# CLKs.net
KiCad netlist of a schematic drawn in Altium Designer
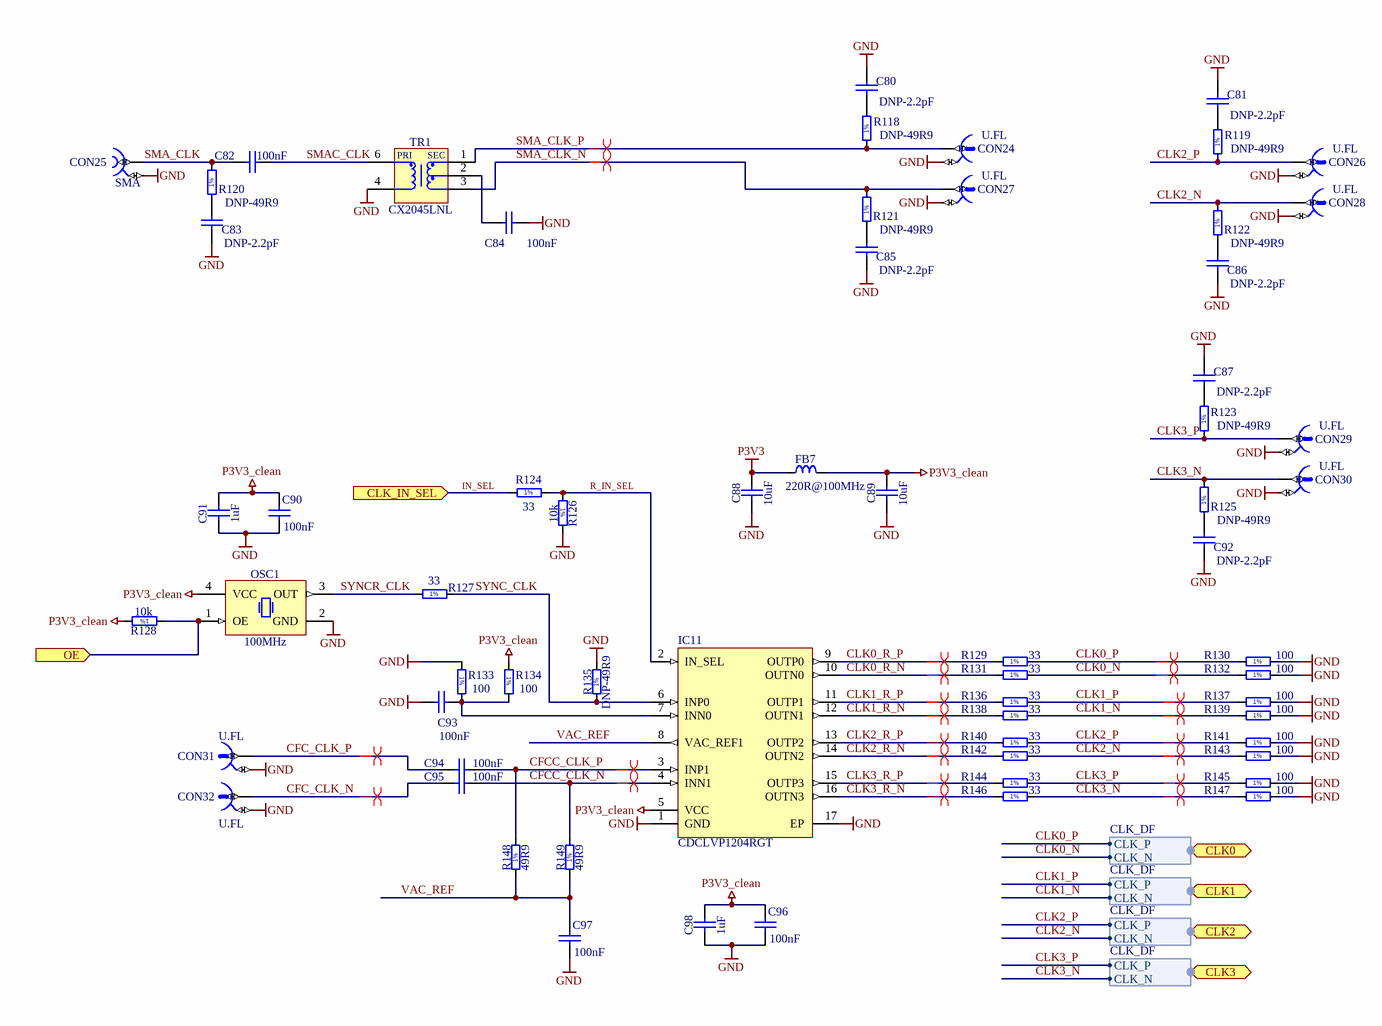
[diagram p0: CLKs.SchDoc]

(export (version "E")
  (design (tool "Eeschema 10.0.6"))
  (components
    (comp (ref "C80")
      (value "DNP-2.2pF")
      (footprint "CAPC1005X55N")
      (description "Non-polarised capacitor")
      (fields
        (field (name "PART NUMBER") "CC0402_2.2PF_50V_0.25PF_NP0")
        (field (name "VOLTAGE") "50V")
        (field (name "AUTHOR") "CERN DEM JLC")
      )
      (libsource (lib "Capacitors") (part "Capacitor - non polarized"))
    )
    (comp (ref "C81")
      (value "DNP-2.2pF")
      (footprint "CAPC1005X55N")
      (description "Non-polarised capacitor")
      (fields
        (field (name "PART NUMBER") "CC0402_2.2PF_50V_0.25PF_NP0")
        (field (name "VOLTAGE") "50V")
        (field (name "AUTHOR") "CERN DEM JLC")
      )
      (libsource (lib "Capacitors") (part "Capacitor - non polarized"))
    )
    (comp (ref "C82")
      (value "100nF")
      (footprint "CAPC0603X33N")
      (description "Non-polarised capacitor")
      (fields
        (field (name "PART NUMBER") "CC0201_100NF_6.3V_10%_X5R")
        (field (name "VOLTAGE") "6.3V")
        (field (name "AUTHOR") "CERN DEM JLC")
      )
      (libsource (lib "Capacitors") (part "Capacitor - non polarized"))
    )
    (comp (ref "C83")
      (value "DNP-2.2pF")
      (footprint "CAPC1005X55N")
      (description "Non-polarised capacitor")
      (fields
        (field (name "PART NUMBER") "CC0402_2.2PF_50V_0.25PF_NP0")
        (field (name "VOLTAGE") "50V")
        (field (name "AUTHOR") "CERN DEM JLC")
      )
      (libsource (lib "Capacitors") (part "Capacitor - non polarized"))
    )
    (comp (ref "C84")
      (value "100nF")
      (footprint "CAPC0603X33N")
      (description "Non-polarised capacitor")
      (fields
        (field (name "PART NUMBER") "CC0201_100NF_6.3V_10%_X5R")
        (field (name "VOLTAGE") "6.3V")
        (field (name "AUTHOR") "CERN DEM JLC")
      )
      (libsource (lib "Capacitors") (part "Capacitor - non polarized"))
    )
    (comp (ref "C85")
      (value "DNP-2.2pF")
      (footprint "CAPC1005X55N")
      (description "Non-polarised capacitor")
      (fields
        (field (name "PART NUMBER") "CC0402_2.2PF_50V_0.25PF_NP0")
        (field (name "VOLTAGE") "50V")
        (field (name "AUTHOR") "CERN DEM JLC")
      )
      (libsource (lib "Capacitors") (part "Capacitor - non polarized"))
    )
    (comp (ref "C86")
      (value "DNP-2.2pF")
      (footprint "CAPC1005X55N")
      (description "Non-polarised capacitor")
      (fields
        (field (name "PART NUMBER") "CC0402_2.2PF_50V_0.25PF_NP0")
        (field (name "VOLTAGE") "50V")
        (field (name "AUTHOR") "CERN DEM JLC")
      )
      (libsource (lib "Capacitors") (part "Capacitor - non polarized"))
    )
    (comp (ref "C87")
      (value "DNP-2.2pF")
      (footprint "CAPC1005X55N")
      (description "Non-polarised capacitor")
      (fields
        (field (name "PART NUMBER") "CC0402_2.2PF_50V_0.25PF_NP0")
        (field (name "VOLTAGE") "50V")
        (field (name "AUTHOR") "CERN DEM JLC")
      )
      (libsource (lib "Capacitors") (part "Capacitor - non polarized"))
    )
    (comp (ref "C88")
      (value "10uF")
      (footprint "CAPC2012X135N")
      (description "Non-polarised capacitor")
      (fields
        (field (name "PART NUMBER") "CC0805_10UF_10V_10%_X7R")
        (field (name "VOLTAGE") "10V")
        (field (name "AUTHOR") "CERN DEM JLC")
      )
      (libsource (lib "Capacitors") (part "Capacitor - non polarized"))
    )
    (comp (ref "C89")
      (value "10uF")
      (footprint "CAPC2012X135N")
      (description "Non-polarised capacitor")
      (fields
        (field (name "PART NUMBER") "CC0805_10UF_10V_10%_X7R")
        (field (name "VOLTAGE") "10V")
        (field (name "AUTHOR") "CERN DEM JLC")
      )
      (libsource (lib "Capacitors") (part "Capacitor - non polarized"))
    )
    (comp (ref "C90")
      (value "100nF")
      (footprint "CAPC0603X33N")
      (description "Non-polarised capacitor")
      (fields
        (field (name "PART NUMBER") "CC0201_100NF_6.3V_10%_X5R")
        (field (name "VOLTAGE") "6.3V")
        (field (name "AUTHOR") "CERN DEM JLC")
      )
      (libsource (lib "Capacitors") (part "Capacitor - non polarized"))
    )
    (comp (ref "C91")
      (value "1uF")
      (footprint "CAPC1608X87N")
      (description "Non-polarised capacitor")
      (fields
        (field (name "PART NUMBER") "CC0603_1UF_25V_10%_X7R")
        (field (name "VOLTAGE") "25V")
        (field (name "AUTHOR") "CERN DEM JLC")
      )
      (libsource (lib "Capacitors") (part "Capacitor - non polarized"))
    )
    (comp (ref "C92")
      (value "DNP-2.2pF")
      (footprint "CAPC1005X55N")
      (description "Non-polarised capacitor")
      (fields
        (field (name "PART NUMBER") "CC0402_2.2PF_50V_0.25PF_NP0")
        (field (name "VOLTAGE") "50V")
        (field (name "AUTHOR") "CERN DEM JLC")
      )
      (libsource (lib "Capacitors") (part "Capacitor - non polarized"))
    )
    (comp (ref "C93")
      (value "100nF")
      (footprint "CAPC1005X55N")
      (description "Non-polarised capacitor")
      (fields
        (field (name "PART NUMBER") "CC0402_100NF_16V_10%_X7R")
        (field (name "VOLTAGE") "16V")
        (field (name "AUTHOR") "CERN DEM JLC")
      )
      (libsource (lib "Capacitors") (part "Capacitor - non polarized"))
    )
    (comp (ref "C94")
      (value "100nF")
      (footprint "CAPC0603X33N")
      (description "Non-polarised capacitor")
      (fields
        (field (name "PART NUMBER") "CC0201_100NF_6.3V_10%_X5R")
        (field (name "VOLTAGE") "6.3V")
        (field (name "AUTHOR") "CERN DEM JLC")
      )
      (libsource (lib "Capacitors") (part "Capacitor - non polarized"))
    )
    (comp (ref "C95")
      (value "100nF")
      (footprint "CAPC0603X33N")
      (description "Non-polarised capacitor")
      (fields
        (field (name "PART NUMBER") "CC0201_100NF_6.3V_10%_X5R")
        (field (name "VOLTAGE") "6.3V")
        (field (name "AUTHOR") "CERN DEM JLC")
      )
      (libsource (lib "Capacitors") (part "Capacitor - non polarized"))
    )
    (comp (ref "C96")
      (value "100nF")
      (footprint "CAPC0603X33N")
      (description "Non-polarised capacitor")
      (fields
        (field (name "PART NUMBER") "CC0201_100NF_6.3V_10%_X5R")
        (field (name "VOLTAGE") "6.3V")
        (field (name "AUTHOR") "CERN DEM JLC")
      )
      (libsource (lib "Capacitors") (part "Capacitor - non polarized"))
    )
    (comp (ref "C97")
      (value "100nF")
      (footprint "CAPC1005X55N")
      (description "Non-polarised capacitor")
      (fields
        (field (name "PART NUMBER") "CC0402_100NF_16V_10%_X7R")
        (field (name "VOLTAGE") "16V")
        (field (name "AUTHOR") "CERN DEM JLC")
      )
      (libsource (lib "Capacitors") (part "Capacitor - non polarized"))
    )
    (comp (ref "C98")
      (value "1uF")
      (footprint "CAPC1608X87N")
      (description "Non-polarised capacitor")
      (fields
        (field (name "PART NUMBER") "CC0603_1UF_25V_10%_X7R")
        (field (name "VOLTAGE") "25V")
        (field (name "AUTHOR") "CERN DEM JLC")
      )
      (libsource (lib "Capacitors") (part "Capacitor - non polarized"))
    )
    (comp (ref "CON24")
      (value "U.FL")
      (footprint "HIROSE_U.FL-R-SMT-1(10)")
      (fields
        (field (name "PART NUMBER") "HIROSE_U.FL-R-SMT-1(10)")
        (field (name "MANUFACTURER") "HIROSE (HRS)")
        (field (name "MANUFACTURER PART NUMBER") "U.FL-R-SMT-1(10)")
        (field (name "AUTHOR") "CERN DEM JLC")
      )
      (libsource (lib "Connectors") (part "Coax_1Male_1Shield"))
    )
    (comp (ref "CON25")
      (value "SMA")
      (footprint "HUBER-SUHNER_85 SMA-50-0-101/111 NE")
      (fields
        (field (name "PART NUMBER") "HUBER-SUHNER_85_SMA-50-0-101/111_NE")
        (field (name "MANUFACTURER") "HUBER+SUHNER")
        (field (name "MANUFACTURER PART NUMBER") "85_SMA-50-0-101/111_NE")
        (field (name "AUTHOR") "CERN DEM JLC")
      )
      (libsource (lib "Connectors") (part "Coax_1Female_1Shield"))
    )
    (comp (ref "CON26")
      (value "U.FL")
      (footprint "HIROSE_U.FL-R-SMT-1(10)")
      (fields
        (field (name "PART NUMBER") "HIROSE_U.FL-R-SMT-1(10)")
        (field (name "MANUFACTURER") "HIROSE (HRS)")
        (field (name "MANUFACTURER PART NUMBER") "U.FL-R-SMT-1(10)")
        (field (name "AUTHOR") "CERN DEM JLC")
      )
      (libsource (lib "Connectors") (part "Coax_1Male_1Shield"))
    )
    (comp (ref "CON27")
      (value "U.FL")
      (footprint "HIROSE_U.FL-R-SMT-1(10)")
      (fields
        (field (name "PART NUMBER") "HIROSE_U.FL-R-SMT-1(10)")
        (field (name "MANUFACTURER") "HIROSE (HRS)")
        (field (name "MANUFACTURER PART NUMBER") "U.FL-R-SMT-1(10)")
        (field (name "AUTHOR") "CERN DEM JLC")
      )
      (libsource (lib "Connectors") (part "Coax_1Male_1Shield"))
    )
    (comp (ref "CON28")
      (value "U.FL")
      (footprint "HIROSE_U.FL-R-SMT-1(10)")
      (fields
        (field (name "PART NUMBER") "HIROSE_U.FL-R-SMT-1(10)")
        (field (name "MANUFACTURER") "HIROSE (HRS)")
        (field (name "MANUFACTURER PART NUMBER") "U.FL-R-SMT-1(10)")
        (field (name "AUTHOR") "CERN DEM JLC")
      )
      (libsource (lib "Connectors") (part "Coax_1Male_1Shield"))
    )
    (comp (ref "CON29")
      (value "U.FL")
      (footprint "HIROSE_U.FL-R-SMT-1(10)")
      (fields
        (field (name "PART NUMBER") "HIROSE_U.FL-R-SMT-1(10)")
        (field (name "MANUFACTURER") "HIROSE (HRS)")
        (field (name "MANUFACTURER PART NUMBER") "U.FL-R-SMT-1(10)")
        (field (name "AUTHOR") "CERN DEM JLC")
      )
      (libsource (lib "Connectors") (part "Coax_1Male_1Shield"))
    )
    (comp (ref "CON30")
      (value "U.FL")
      (footprint "HIROSE_U.FL-R-SMT-1(10)")
      (fields
        (field (name "PART NUMBER") "HIROSE_U.FL-R-SMT-1(10)")
        (field (name "MANUFACTURER") "HIROSE (HRS)")
        (field (name "MANUFACTURER PART NUMBER") "U.FL-R-SMT-1(10)")
        (field (name "AUTHOR") "CERN DEM JLC")
      )
      (libsource (lib "Connectors") (part "Coax_1Male_1Shield"))
    )
    (comp (ref "CON31")
      (value "U.FL")
      (footprint "HIROSE_U.FL-R-SMT-1(10)")
      (fields
        (field (name "PART NUMBER") "HIROSE_U.FL-R-SMT-1(10)")
        (field (name "MANUFACTURER") "HIROSE (HRS)")
        (field (name "MANUFACTURER PART NUMBER") "U.FL-R-SMT-1(10)")
        (field (name "AUTHOR") "CERN DEM JLC")
      )
      (libsource (lib "") (part "Coax_1Male_1Shield_1"))
    )
    (comp (ref "CON32")
      (value "U.FL")
      (footprint "HIROSE_U.FL-R-SMT-1(10)")
      (fields
        (field (name "PART NUMBER") "HIROSE_U.FL-R-SMT-1(10)")
        (field (name "MANUFACTURER") "HIROSE (HRS)")
        (field (name "MANUFACTURER PART NUMBER") "U.FL-R-SMT-1(10)")
        (field (name "AUTHOR") "CERN DEM JLC")
      )
      (libsource (lib "") (part "Coax_1Male_1Shield_1"))
    )
    (comp (ref "FB7")
      (value "220R@100MHz")
      (footprint "INDC2012X105N")
      (description "Inductor")
      (fields
        (field (name "PART NUMBER") "IND0805_MURATA_BLM21PG221SN1D")
        (field (name "POWER") "2A")
        (field (name "AUTHOR") "CERN DEM JLC")
      )
      (libsource (lib "Inductors & Transformers") (part "Inductor"))
    )
    (comp (ref "IC11")
      (value "CDCLVP1204RGT")
      (footprint "QFN50P300X300X100-17N-S165")
      (description "2:2 Low Additive Jitter LVPECL Buffer")
      (libsource (lib "TJ_LIB") (part "CDCLVP1204RGT"))
    )
    (comp (ref "OSC1")
      (value "100MHz")
      (footprint "OSC_EPSON_SG-8002CA")
      (description "Oscillator 4 pins 1=OE 2=GND 3=OUT 4=VCC")
      (fields
        (field (name "PART NUMBER") "OSC_100MHZ_EPSON_SG-8002CAPCB100MHZ")
        (field (name "MANUFACTURER") "EPSON-TOYOCOM")
        (field (name "AUTHOR") "CERN DEM JLC")
      )
      (libsource (lib "ICs And Semiconductors") (part "Oscillator 1OE 2GND 3OUT 4VCC"))
    )
    (comp (ref "R118")
      (value "DNP-49R9")
      (footprint "RESC1005X40N")
      (description "Resistor - 1%")
      (fields
        (field (name "PART NUMBER") "R0402_49R9_1%_0.0625W_100PPM")
        (field (name "POWER") "0.0625W")
        (field (name "AUTHOR") "CERN DEM JLC")
      )
      (libsource (lib "Resistors") (part "Resistor - 1%"))
    )
    (comp (ref "R119")
      (value "DNP-49R9")
      (footprint "RESC1005X40N")
      (description "Resistor - 1%")
      (fields
        (field (name "PART NUMBER") "R0402_49R9_1%_0.0625W_100PPM")
        (field (name "POWER") "0.0625W")
        (field (name "AUTHOR") "CERN DEM JLC")
      )
      (libsource (lib "Resistors") (part "Resistor - 1%"))
    )
    (comp (ref "R120")
      (value "DNP-49R9")
      (footprint "RESC1005X40N")
      (description "Resistor - 1%")
      (fields
        (field (name "PART NUMBER") "R0402_49R9_1%_0.0625W_100PPM")
        (field (name "POWER") "0.0625W")
        (field (name "AUTHOR") "CERN DEM JLC")
      )
      (libsource (lib "Resistors") (part "Resistor - 1%"))
    )
    (comp (ref "R121")
      (value "DNP-49R9")
      (footprint "RESC1005X40N")
      (description "Resistor - 1%")
      (fields
        (field (name "PART NUMBER") "R0402_49R9_1%_0.0625W_100PPM")
        (field (name "POWER") "0.0625W")
        (field (name "AUTHOR") "CERN DEM JLC")
      )
      (libsource (lib "Resistors") (part "Resistor - 1%"))
    )
    (comp (ref "R122")
      (value "DNP-49R9")
      (footprint "RESC1005X40N")
      (description "Resistor - 1%")
      (fields
        (field (name "PART NUMBER") "R0402_49R9_1%_0.0625W_100PPM")
        (field (name "POWER") "0.0625W")
        (field (name "AUTHOR") "CERN DEM JLC")
      )
      (libsource (lib "Resistors") (part "Resistor - 1%"))
    )
    (comp (ref "R123")
      (value "DNP-49R9")
      (footprint "RESC1005X40N")
      (description "Resistor - 1%")
      (fields
        (field (name "PART NUMBER") "R0402_49R9_1%_0.0625W_100PPM")
        (field (name "POWER") "0.0625W")
        (field (name "AUTHOR") "CERN DEM JLC")
      )
      (libsource (lib "Resistors") (part "Resistor - 1%"))
    )
    (comp (ref "R124")
      (value "33")
      (footprint "RESC1005X40N")
      (description "Resistor - 1%")
      (fields
        (field (name "PART NUMBER") "R0402_33R_1%_0.0625W_100PPM")
        (field (name "POWER") "0.0625W")
        (field (name "AUTHOR") "CERN DEM JLC")
      )
      (libsource (lib "Resistors") (part "Resistor - 1%"))
    )
    (comp (ref "R125")
      (value "DNP-49R9")
      (footprint "RESC1005X40N")
      (description "Resistor - 1%")
      (fields
        (field (name "PART NUMBER") "R0402_49R9_1%_0.0625W_100PPM")
        (field (name "POWER") "0.0625W")
        (field (name "AUTHOR") "CERN DEM JLC")
      )
      (libsource (lib "Resistors") (part "Resistor - 1%"))
    )
    (comp (ref "R126")
      (value "10k")
      (footprint "RESC1005X40N")
      (description "Resistor - 1%")
      (fields
        (field (name "PART NUMBER") "R0402_10K_1%_0.0625W_100PPM")
        (field (name "POWER") "0.0625W")
        (field (name "AUTHOR") "CERN DEM JLC")
      )
      (libsource (lib "Resistors") (part "Resistor - 1%"))
    )
    (comp (ref "R127")
      (value "33")
      (footprint "RESC1005X40N")
      (description "Resistor - 1%")
      (fields
        (field (name "PART NUMBER") "R0402_33R_1%_0.0625W_100PPM")
        (field (name "POWER") "0.0625W")
        (field (name "AUTHOR") "CERN DEM JLC")
      )
      (libsource (lib "Resistors") (part "Resistor - 1%"))
    )
    (comp (ref "R128")
      (value "10k")
      (footprint "RESC1005X40N")
      (description "Resistor - 1%")
      (fields
        (field (name "PART NUMBER") "R0402_10K_1%_0.0625W_100PPM")
        (field (name "POWER") "0.0625W")
        (field (name "AUTHOR") "CERN DEM JLC")
      )
      (libsource (lib "Resistors") (part "Resistor - 1%"))
    )
    (comp (ref "R129")
      (value "33")
      (footprint "RESC1005X40N")
      (description "Resistor - 1%")
      (fields
        (field (name "PART NUMBER") "R0402_33R_1%_0.0625W_100PPM")
        (field (name "POWER") "0.0625W")
        (field (name "AUTHOR") "CERN DEM JLC")
      )
      (libsource (lib "Resistors") (part "Resistor - 1%"))
    )
    (comp (ref "R130")
      (value "100")
      (footprint "RESC1005X40N")
      (description "Resistor - 1%")
      (fields
        (field (name "PART NUMBER") "R0402_100R_1%_0.0625W_100PPM")
        (field (name "POWER") "0.0625W")
        (field (name "AUTHOR") "CERN DEM JLC")
      )
      (libsource (lib "Resistors") (part "Resistor - 1%"))
    )
    (comp (ref "R131")
      (value "33")
      (footprint "RESC1005X40N")
      (description "Resistor - 1%")
      (fields
        (field (name "PART NUMBER") "R0402_33R_1%_0.0625W_100PPM")
        (field (name "POWER") "0.0625W")
        (field (name "AUTHOR") "CERN DEM JLC")
      )
      (libsource (lib "Resistors") (part "Resistor - 1%"))
    )
    (comp (ref "R132")
      (value "100")
      (footprint "RESC1005X40N")
      (description "Resistor - 1%")
      (fields
        (field (name "PART NUMBER") "R0402_100R_1%_0.0625W_100PPM")
        (field (name "POWER") "0.0625W")
        (field (name "AUTHOR") "CERN DEM JLC")
      )
      (libsource (lib "Resistors") (part "Resistor - 1%"))
    )
    (comp (ref "R133")
      (value "100")
      (footprint "RESC1005X40N")
      (description "Resistor - 1%")
      (fields
        (field (name "PART NUMBER") "R0402_100R_1%_0.0625W_100PPM")
        (field (name "POWER") "0.0625W")
        (field (name "AUTHOR") "CERN DEM JLC")
      )
      (libsource (lib "Resistors") (part "Resistor - 1%"))
    )
    (comp (ref "R134")
      (value "100")
      (footprint "RESC1005X40N")
      (description "Resistor - 1%")
      (fields
        (field (name "PART NUMBER") "R0402_100R_1%_0.0625W_100PPM")
        (field (name "POWER") "0.0625W")
        (field (name "AUTHOR") "CERN DEM JLC")
      )
      (libsource (lib "Resistors") (part "Resistor - 1%"))
    )
    (comp (ref "R135")
      (value "DNP-49R9")
      (footprint "RESC1005X40N")
      (description "Resistor - 1%")
      (fields
        (field (name "PART NUMBER") "R0402_49R9_1%_0.0625W_100PPM")
        (field (name "POWER") "0.0625W")
        (field (name "AUTHOR") "CERN DEM JLC")
      )
      (libsource (lib "Resistors") (part "Resistor - 1%"))
    )
    (comp (ref "R136")
      (value "33")
      (footprint "RESC1005X40N")
      (description "Resistor - 1%")
      (fields
        (field (name "PART NUMBER") "R0402_33R_1%_0.0625W_100PPM")
        (field (name "POWER") "0.0625W")
        (field (name "AUTHOR") "CERN DEM JLC")
      )
      (libsource (lib "Resistors") (part "Resistor - 1%"))
    )
    (comp (ref "R137")
      (value "100")
      (footprint "RESC1005X40N")
      (description "Resistor - 1%")
      (fields
        (field (name "PART NUMBER") "R0402_100R_1%_0.0625W_100PPM")
        (field (name "POWER") "0.0625W")
        (field (name "AUTHOR") "CERN DEM JLC")
      )
      (libsource (lib "Resistors") (part "Resistor - 1%"))
    )
    (comp (ref "R138")
      (value "33")
      (footprint "RESC1005X40N")
      (description "Resistor - 1%")
      (fields
        (field (name "PART NUMBER") "R0402_33R_1%_0.0625W_100PPM")
        (field (name "POWER") "0.0625W")
        (field (name "AUTHOR") "CERN DEM JLC")
      )
      (libsource (lib "Resistors") (part "Resistor - 1%"))
    )
    (comp (ref "R139")
      (value "100")
      (footprint "RESC1005X40N")
      (description "Resistor - 1%")
      (fields
        (field (name "PART NUMBER") "R0402_100R_1%_0.0625W_100PPM")
        (field (name "POWER") "0.0625W")
        (field (name "AUTHOR") "CERN DEM JLC")
      )
      (libsource (lib "Resistors") (part "Resistor - 1%"))
    )
    (comp (ref "R140")
      (value "33")
      (footprint "RESC1005X40N")
      (description "Resistor - 1%")
      (fields
        (field (name "PART NUMBER") "R0402_33R_1%_0.0625W_100PPM")
        (field (name "POWER") "0.0625W")
        (field (name "AUTHOR") "CERN DEM JLC")
      )
      (libsource (lib "Resistors") (part "Resistor - 1%"))
    )
    (comp (ref "R141")
      (value "100")
      (footprint "RESC1005X40N")
      (description "Resistor - 1%")
      (fields
        (field (name "PART NUMBER") "R0402_100R_1%_0.0625W_100PPM")
        (field (name "POWER") "0.0625W")
        (field (name "AUTHOR") "CERN DEM JLC")
      )
      (libsource (lib "Resistors") (part "Resistor - 1%"))
    )
    (comp (ref "R142")
      (value "33")
      (footprint "RESC1005X40N")
      (description "Resistor - 1%")
      (fields
        (field (name "PART NUMBER") "R0402_33R_1%_0.0625W_100PPM")
        (field (name "POWER") "0.0625W")
        (field (name "AUTHOR") "CERN DEM JLC")
      )
      (libsource (lib "Resistors") (part "Resistor - 1%"))
    )
    (comp (ref "R143")
      (value "100")
      (footprint "RESC1005X40N")
      (description "Resistor - 1%")
      (fields
        (field (name "PART NUMBER") "R0402_100R_1%_0.0625W_100PPM")
        (field (name "POWER") "0.0625W")
        (field (name "AUTHOR") "CERN DEM JLC")
      )
      (libsource (lib "Resistors") (part "Resistor - 1%"))
    )
    (comp (ref "R144")
      (value "33")
      (footprint "RESC1005X40N")
      (description "Resistor - 1%")
      (fields
        (field (name "PART NUMBER") "R0402_33R_1%_0.0625W_100PPM")
        (field (name "POWER") "0.0625W")
        (field (name "AUTHOR") "CERN DEM JLC")
      )
      (libsource (lib "Resistors") (part "Resistor - 1%"))
    )
    (comp (ref "R145")
      (value "100")
      (footprint "RESC1005X40N")
      (description "Resistor - 1%")
      (fields
        (field (name "PART NUMBER") "R0402_100R_1%_0.0625W_100PPM")
        (field (name "POWER") "0.0625W")
        (field (name "AUTHOR") "CERN DEM JLC")
      )
      (libsource (lib "Resistors") (part "Resistor - 1%"))
    )
    (comp (ref "R146")
      (value "33")
      (footprint "RESC1005X40N")
      (description "Resistor - 1%")
      (fields
        (field (name "PART NUMBER") "R0402_33R_1%_0.0625W_100PPM")
        (field (name "POWER") "0.0625W")
        (field (name "AUTHOR") "CERN DEM JLC")
      )
      (libsource (lib "Resistors") (part "Resistor - 1%"))
    )
    (comp (ref "R147")
      (value "100")
      (footprint "RESC1005X40N")
      (description "Resistor - 1%")
      (fields
        (field (name "PART NUMBER") "R0402_100R_1%_0.0625W_100PPM")
        (field (name "POWER") "0.0625W")
        (field (name "AUTHOR") "CERN DEM JLC")
      )
      (libsource (lib "Resistors") (part "Resistor - 1%"))
    )
    (comp (ref "R148")
      (value "49R9")
      (footprint "RESC1005X40N")
      (description "Resistor - 1%")
      (fields
        (field (name "PART NUMBER") "R0402_49R9_1%_0.0625W_100PPM")
        (field (name "POWER") "0.0625W")
        (field (name "AUTHOR") "CERN DEM JLC")
      )
      (libsource (lib "Resistors") (part "Resistor - 1%"))
    )
    (comp (ref "R149")
      (value "49R9")
      (footprint "RESC1005X40N")
      (description "Resistor - 1%")
      (fields
        (field (name "PART NUMBER") "R0402_49R9_1%_0.0625W_100PPM")
        (field (name "POWER") "0.0625W")
        (field (name "AUTHOR") "CERN DEM JLC")
      )
      (libsource (lib "Resistors") (part "Resistor - 1%"))
    )
    (comp (ref "TR1")
      (value "CX2045LNL")
      (footprint "PULSE_CX2045LNL")
      (description "Balun (Ruthroff Balun Transformer) Impedance - Unbalanced/Balanced 1:2 (1:1.41 Turn Ratio)")
      (libsource (lib "TJ_LIB") (part "PULSE_CX2045LNL"))
    )
  )
  (nets
    (net (code "2") (name "/CFCC_CLK_N") (class "Default")
      (node (ref "C95") (pin "1") (pinfunction "1_1") (pintype "passive"))
      (node (ref "IC11") (pin "4") (pinfunction "INN1_4") (pintype "input"))
      (node (ref "R149") (pin "2") (pinfunction "2_2") (pintype "passive"))
    )
    (net (code "3") (name "/CFCC_CLK_P") (class "Default")
      (node (ref "C94") (pin "1") (pinfunction "1_1") (pintype "passive"))
      (node (ref "IC11") (pin "3") (pinfunction "INP1_3") (pintype "input"))
      (node (ref "R148") (pin "2") (pinfunction "2_2") (pintype "passive"))
    )
    (net (code "4") (name "/CFC_CLK_N") (class "Default")
      (node (ref "C95") (pin "2") (pinfunction "2_2") (pintype "passive"))
      (node (ref "CON32") (pin "1") (pinfunction "1_1") (pintype "bidirectional"))
    )
    (net (code "5") (name "/CFC_CLK_P") (class "Default")
      (node (ref "C94") (pin "2") (pinfunction "2_2") (pintype "passive"))
      (node (ref "CON31") (pin "1") (pinfunction "1_1") (pintype "bidirectional"))
    )
    (net (code "6") (name "/CLK0_N") (class "Default")
      (node (ref "R131") (pin "2") (pinfunction "2_2") (pintype "passive"))
      (node (ref "R132") (pin "1") (pinfunction "1_1") (pintype "passive"))
    )
    (net (code "7") (name "/CLK0_P") (class "Default")
      (node (ref "R129") (pin "2") (pinfunction "2_2") (pintype "passive"))
      (node (ref "R130") (pin "1") (pinfunction "1_1") (pintype "passive"))
    )
    (net (code "8") (name "/CLK0_R_N") (class "Default")
      (node (ref "IC11") (pin "10") (pinfunction "OUTN0_10") (pintype "output"))
      (node (ref "R131") (pin "1") (pinfunction "1_1") (pintype "passive"))
    )
    (net (code "9") (name "/CLK0_R_P") (class "Default")
      (node (ref "IC11") (pin "9") (pinfunction "OUTP0_9") (pintype "output"))
      (node (ref "R129") (pin "1") (pinfunction "1_1") (pintype "passive"))
    )
    (net (code "10") (name "/CLK1_N") (class "Default")
      (node (ref "R138") (pin "2") (pinfunction "2_2") (pintype "passive"))
      (node (ref "R139") (pin "1") (pinfunction "1_1") (pintype "passive"))
    )
    (net (code "11") (name "/CLK1_P") (class "Default")
      (node (ref "R136") (pin "2") (pinfunction "2_2") (pintype "passive"))
      (node (ref "R137") (pin "1") (pinfunction "1_1") (pintype "passive"))
    )
    (net (code "12") (name "/CLK1_R_N") (class "Default")
      (node (ref "IC11") (pin "12") (pinfunction "OUTN1_12") (pintype "output"))
      (node (ref "R138") (pin "1") (pinfunction "1_1") (pintype "passive"))
    )
    (net (code "13") (name "/CLK1_R_P") (class "Default")
      (node (ref "IC11") (pin "11") (pinfunction "OUTP1_11") (pintype "output"))
      (node (ref "R136") (pin "1") (pinfunction "1_1") (pintype "passive"))
    )
    (net (code "14") (name "/CLK2_N") (class "Default")
      (node (ref "CON28") (pin "1") (pinfunction "1_1") (pintype "bidirectional"))
      (node (ref "R122") (pin "2") (pinfunction "2_2") (pintype "passive"))
      (node (ref "R142") (pin "2") (pinfunction "2_2") (pintype "passive"))
      (node (ref "R143") (pin "1") (pinfunction "1_1") (pintype "passive"))
    )
    (net (code "15") (name "/CLK2_P") (class "Default")
      (node (ref "CON26") (pin "1") (pinfunction "1_1") (pintype "bidirectional"))
      (node (ref "R119") (pin "1") (pinfunction "1_1") (pintype "passive"))
      (node (ref "R140") (pin "2") (pinfunction "2_2") (pintype "passive"))
      (node (ref "R141") (pin "1") (pinfunction "1_1") (pintype "passive"))
    )
    (net (code "16") (name "/CLK2_R_N") (class "Default")
      (node (ref "IC11") (pin "14") (pinfunction "OUTN2_14") (pintype "output"))
      (node (ref "R142") (pin "1") (pinfunction "1_1") (pintype "passive"))
    )
    (net (code "17") (name "/CLK2_R_P") (class "Default")
      (node (ref "IC11") (pin "13") (pinfunction "OUTP2_13") (pintype "output"))
      (node (ref "R140") (pin "1") (pinfunction "1_1") (pintype "passive"))
    )
    (net (code "18") (name "/CLK3_N") (class "Default")
      (node (ref "CON30") (pin "1") (pinfunction "1_1") (pintype "bidirectional"))
      (node (ref "R125") (pin "2") (pinfunction "2_2") (pintype "passive"))
      (node (ref "R146") (pin "2") (pinfunction "2_2") (pintype "passive"))
      (node (ref "R147") (pin "1") (pinfunction "1_1") (pintype "passive"))
    )
    (net (code "19") (name "/CLK3_P") (class "Default")
      (node (ref "CON29") (pin "1") (pinfunction "1_1") (pintype "bidirectional"))
      (node (ref "R123") (pin "1") (pinfunction "1_1") (pintype "passive"))
      (node (ref "R144") (pin "2") (pinfunction "2_2") (pintype "passive"))
      (node (ref "R145") (pin "1") (pinfunction "1_1") (pintype "passive"))
    )
    (net (code "20") (name "/CLK3_R_N") (class "Default")
      (node (ref "IC11") (pin "16") (pinfunction "OUTN3_16") (pintype "output"))
      (node (ref "R146") (pin "1") (pinfunction "1_1") (pintype "passive"))
    )
    (net (code "21") (name "/CLK3_R_P") (class "Default")
      (node (ref "IC11") (pin "15") (pinfunction "OUTP3_15") (pintype "output"))
      (node (ref "R144") (pin "1") (pinfunction "1_1") (pintype "passive"))
    )
    (net (code "22") (name "/IN_SEL") (class "Default")
      (node (ref "R124") (pin "1") (pinfunction "1_1") (pintype "passive"))
    )
    (net (code "23") (name "/OE") (class "Default")
      (node (ref "OSC1") (pin "1") (pinfunction "OE_1") (pintype "input"))
      (node (ref "R128") (pin "1") (pinfunction "1_1") (pintype "passive"))
    )
    (net (code "24") (name "/R_IN_SEL") (class "Default")
      (node (ref "IC11") (pin "2") (pinfunction "IN_SEL_2") (pintype "input"))
      (node (ref "R124") (pin "2") (pinfunction "2_2") (pintype "passive"))
      (node (ref "R126") (pin "1") (pinfunction "1_1") (pintype "passive"))
    )
    (net (code "25") (name "/SMAC_CLK") (class "Default")
      (node (ref "C82") (pin "1") (pinfunction "1_1") (pintype "passive"))
      (node (ref "TR1") (pin "6") (pinfunction "6_6") (pintype "passive"))
    )
    (net (code "26") (name "/SMA_CLK") (class "Default")
      (node (ref "C82") (pin "2") (pinfunction "2_2") (pintype "passive"))
      (node (ref "CON25") (pin "1") (pinfunction "1_1") (pintype "bidirectional"))
      (node (ref "R120") (pin "2") (pinfunction "2_2") (pintype "passive"))
    )
    (net (code "27") (name "/SMA_CLK_N") (class "Default")
      (node (ref "CON27") (pin "1") (pinfunction "1_1") (pintype "bidirectional"))
      (node (ref "R121") (pin "2") (pinfunction "2_2") (pintype "passive"))
      (node (ref "TR1") (pin "3") (pinfunction "3_3") (pintype "passive"))
    )
    (net (code "28") (name "/SMA_CLK_P") (class "Default")
      (node (ref "CON24") (pin "1") (pinfunction "1_1") (pintype "bidirectional"))
      (node (ref "R118") (pin "1") (pinfunction "1_1") (pintype "passive"))
      (node (ref "TR1") (pin "1") (pinfunction "1_1") (pintype "passive"))
    )
    (net (code "29") (name "/SYNCR_CLK") (class "Default")
      (node (ref "OSC1") (pin "3") (pinfunction "OUT_3") (pintype "output"))
      (node (ref "R127") (pin "1") (pinfunction "1_1") (pintype "passive"))
    )
    (net (code "30") (name "/SYNC_CLK") (class "Default")
      (node (ref "IC11") (pin "6") (pinfunction "INP0_6") (pintype "input"))
      (node (ref "R127") (pin "2") (pinfunction "2_2") (pintype "passive"))
      (node (ref "R135") (pin "1") (pinfunction "1_1") (pintype "passive"))
    )
    (net (code "31") (name "/VAC_REF") (class "Default")
      (node (ref "C97") (pin "2") (pinfunction "2_2") (pintype "passive"))
      (node (ref "IC11") (pin "8") (pinfunction "VAC_REF1_8") (pintype "output"))
      (node (ref "R148") (pin "1") (pinfunction "1_1") (pintype "passive"))
      (node (ref "R149") (pin "1") (pinfunction "1_1") (pintype "passive"))
    )
    (net (code "33") (name "GND") (class "Default")
      (node (ref "C80") (pin "2") (pinfunction "2_2") (pintype "passive"))
      (node (ref "C81") (pin "2") (pinfunction "2_2") (pintype "passive"))
      (node (ref "C83") (pin "2") (pinfunction "2_2") (pintype "passive"))
      (node (ref "C84") (pin "1") (pinfunction "1_1") (pintype "passive"))
      (node (ref "C85") (pin "2") (pinfunction "2_2") (pintype "passive"))
      (node (ref "C86") (pin "2") (pinfunction "2_2") (pintype "passive"))
      (node (ref "C87") (pin "2") (pinfunction "2_2") (pintype "passive"))
      (node (ref "C88") (pin "1") (pinfunction "1_1") (pintype "passive"))
      (node (ref "C89") (pin "1") (pinfunction "1_1") (pintype "passive"))
      (node (ref "C90") (pin "1") (pinfunction "1_1") (pintype "passive"))
      (node (ref "C91") (pin "1") (pinfunction "1_1") (pintype "passive"))
      (node (ref "C92") (pin "2") (pinfunction "2_2") (pintype "passive"))
      (node (ref "C93") (pin "1") (pinfunction "1_1") (pintype "passive"))
      (node (ref "C96") (pin "1") (pinfunction "1_1") (pintype "passive"))
      (node (ref "C97") (pin "1") (pinfunction "1_1") (pintype "passive"))
      (node (ref "C98") (pin "1") (pinfunction "1_1") (pintype "passive"))
      (node (ref "CON24") (pin "2") (pinfunction "2_2") (pintype "bidirectional"))
      (node (ref "CON25") (pin "2") (pinfunction "2_2") (pintype "bidirectional"))
      (node (ref "CON26") (pin "2") (pinfunction "2_2") (pintype "bidirectional"))
      (node (ref "CON27") (pin "2") (pinfunction "2_2") (pintype "bidirectional"))
      (node (ref "CON28") (pin "2") (pinfunction "2_2") (pintype "bidirectional"))
      (node (ref "CON29") (pin "2") (pinfunction "2_2") (pintype "bidirectional"))
      (node (ref "CON30") (pin "2") (pinfunction "2_2") (pintype "bidirectional"))
      (node (ref "CON31") (pin "2") (pinfunction "2_2") (pintype "bidirectional"))
      (node (ref "CON32") (pin "2") (pinfunction "2_2") (pintype "bidirectional"))
      (node (ref "IC11") (pin "1") (pinfunction "GND_1") (pintype "power_in"))
      (node (ref "IC11") (pin "17") (pinfunction "EP_17") (pintype "power_in"))
      (node (ref "OSC1") (pin "2") (pinfunction "GND_2") (pintype "power_in"))
      (node (ref "R126") (pin "2") (pinfunction "2_2") (pintype "passive"))
      (node (ref "R130") (pin "2") (pinfunction "2_2") (pintype "passive"))
      (node (ref "R132") (pin "2") (pinfunction "2_2") (pintype "passive"))
      (node (ref "R133") (pin "1") (pinfunction "1_1") (pintype "passive"))
      (node (ref "R135") (pin "2") (pinfunction "2_2") (pintype "passive"))
      (node (ref "R137") (pin "2") (pinfunction "2_2") (pintype "passive"))
      (node (ref "R139") (pin "2") (pinfunction "2_2") (pintype "passive"))
      (node (ref "R141") (pin "2") (pinfunction "2_2") (pintype "passive"))
      (node (ref "R143") (pin "2") (pinfunction "2_2") (pintype "passive"))
      (node (ref "R145") (pin "2") (pinfunction "2_2") (pintype "passive"))
      (node (ref "R147") (pin "2") (pinfunction "2_2") (pintype "passive"))
      (node (ref "TR1") (pin "4") (pinfunction "4_4") (pintype "passive"))
    )
    (net (code "34") (name "Net-(C80-Pad1)") (class "Default")
      (node (ref "C80") (pin "1") (pinfunction "1_1") (pintype "passive"))
      (node (ref "R118") (pin "2") (pinfunction "2_2") (pintype "passive"))
    )
    (net (code "35") (name "Net-(C81-Pad1)") (class "Default")
      (node (ref "C81") (pin "1") (pinfunction "1_1") (pintype "passive"))
      (node (ref "R119") (pin "2") (pinfunction "2_2") (pintype "passive"))
    )
    (net (code "36") (name "Net-(C83-Pad1)") (class "Default")
      (node (ref "C83") (pin "1") (pinfunction "1_1") (pintype "passive"))
      (node (ref "R120") (pin "1") (pinfunction "1_1") (pintype "passive"))
    )
    (net (code "37") (name "Net-(C84-Pad2)") (class "Default")
      (node (ref "C84") (pin "2") (pinfunction "2_2") (pintype "passive"))
      (node (ref "TR1") (pin "2") (pinfunction "2_2") (pintype "passive"))
    )
    (net (code "38") (name "Net-(C85-Pad1)") (class "Default")
      (node (ref "C85") (pin "1") (pinfunction "1_1") (pintype "passive"))
      (node (ref "R121") (pin "1") (pinfunction "1_1") (pintype "passive"))
    )
    (net (code "39") (name "Net-(C86-Pad1)") (class "Default")
      (node (ref "C86") (pin "1") (pinfunction "1_1") (pintype "passive"))
      (node (ref "R122") (pin "1") (pinfunction "1_1") (pintype "passive"))
    )
    (net (code "40") (name "Net-(C87-Pad1)") (class "Default")
      (node (ref "C87") (pin "1") (pinfunction "1_1") (pintype "passive"))
      (node (ref "R123") (pin "2") (pinfunction "2_2") (pintype "passive"))
    )
    (net (code "41") (name "Net-(C92-Pad1)") (class "Default")
      (node (ref "C92") (pin "1") (pinfunction "1_1") (pintype "passive"))
      (node (ref "R125") (pin "1") (pinfunction "1_1") (pintype "passive"))
    )
    (net (code "42") (name "Net-(IC11-INN0)") (class "Default")
      (node (ref "C93") (pin "2") (pinfunction "2_2") (pintype "passive"))
      (node (ref "IC11") (pin "7") (pinfunction "INN0_7") (pintype "input"))
      (node (ref "R133") (pin "2") (pinfunction "2_2") (pintype "passive"))
      (node (ref "R134") (pin "2") (pinfunction "2_2") (pintype "passive"))
    )
    (net (code "43") (name "P3V3") (class "Default")
      (node (ref "C88") (pin "2") (pinfunction "2_2") (pintype "passive"))
      (node (ref "FB7") (pin "1") (pinfunction "1_1") (pintype "passive"))
    )
    (net (code "44") (name "P3V3_clean") (class "Default")
      (node (ref "C89") (pin "2") (pinfunction "2_2") (pintype "passive"))
      (node (ref "C90") (pin "2") (pinfunction "2_2") (pintype "passive"))
      (node (ref "C91") (pin "2") (pinfunction "2_2") (pintype "passive"))
      (node (ref "C96") (pin "2") (pinfunction "2_2") (pintype "passive"))
      (node (ref "C98") (pin "2") (pinfunction "2_2") (pintype "passive"))
      (node (ref "FB7") (pin "2") (pinfunction "2_2") (pintype "passive"))
      (node (ref "IC11") (pin "5") (pinfunction "VCC_5") (pintype "power_in"))
      (node (ref "OSC1") (pin "4") (pinfunction "VCC_4") (pintype "power_in"))
      (node (ref "R128") (pin "2") (pinfunction "2_2") (pintype "passive"))
      (node (ref "R134") (pin "1") (pinfunction "1_1") (pintype "passive"))
    )
  )
)
